# WCE_Power_Backscatter.net
KiCad netlist of a schematic drawn in Altium Designer
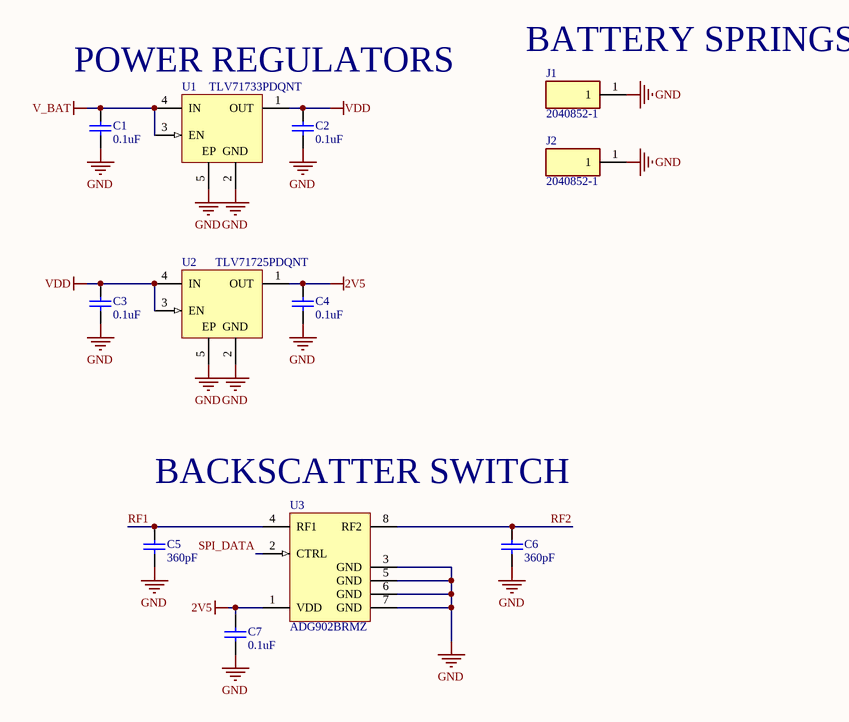
[diagram p0: WCE_Power_Backscatter.SchDoc]

(export (version "E")
  (design (tool "Eeschema 10.0.6"))
  (components
    (comp (ref "C1")
      (value "0.1uF")
      (footprint "CAPC0603X33X15LL03T05")
      (description "Capacitor 0.1 uF 0201 XR5")
      (fields
        (field (name "PART NUMBER") "02016D104KAT2A")
        (field (name "MANUFACTURER") "AVX Interconnect / Elco")
      )
      (libsource (lib "Altium Content Vault") (part "CAP"))
    )
    (comp (ref "C2")
      (value "0.1uF")
      (footprint "CAPC0603X33X15LL03T05")
      (description "Capacitor 0.1 uF 0201 XR5")
      (fields
        (field (name "PART NUMBER") "02016D104KAT2A")
        (field (name "MANUFACTURER") "AVX Interconnect / Elco")
      )
      (libsource (lib "Altium Content Vault") (part "CAP"))
    )
    (comp (ref "C3")
      (value "0.1uF")
      (footprint "CAPC0603X33X15LL03T05")
      (description "Capacitor 0.1 uF 0201 XR5")
      (fields
        (field (name "PART NUMBER") "02016D104KAT2A")
        (field (name "MANUFACTURER") "AVX Interconnect / Elco")
      )
      (libsource (lib "Altium Content Vault") (part "CAP"))
    )
    (comp (ref "C4")
      (value "0.1uF")
      (footprint "CAPC0603X33X15LL03T05")
      (description "Capacitor 0.1 uF 0201 XR5")
      (fields
        (field (name "PART NUMBER") "02016D104KAT2A")
        (field (name "MANUFACTURER") "AVX Interconnect / Elco")
      )
      (libsource (lib "Altium Content Vault") (part "CAP"))
    )
    (comp (ref "C5")
      (value "360pF")
      (footprint "CAPC0603X33X15LL03T05")
      (description "Capacitor 360 pF 0201 XR5")
      (fields
        (field (name "PART NUMBER") "02016D104KAT2A")
        (field (name "MANUFACTURER") "AVX Interconnect / Elco")
      )
      (libsource (lib "Altium Content Vault") (part "CAP"))
    )
    (comp (ref "C6")
      (value "360pF")
      (footprint "CAPC0603X33X15LL03T05")
      (description "Capacitor 360 pF 0201 XR5")
      (fields
        (field (name "PART NUMBER") "02016D104KAT2A")
        (field (name "MANUFACTURER") "AVX Interconnect / Elco")
      )
      (libsource (lib "Altium Content Vault") (part "CAP"))
    )
    (comp (ref "C7")
      (value "0.1uF")
      (footprint "CAPC0603X33X15LL03T05")
      (description "Capacitor 0.1 uF 0201 XR5")
      (fields
        (field (name "PART NUMBER") "02016D104KAT2A")
        (field (name "MANUFACTURER") "AVX Interconnect / Elco")
      )
      (libsource (lib "Altium Content Vault") (part "CAP"))
    )
    (comp (ref "J1")
      (value "2040852-1")
      (footprint "2040852-1")
      (description "TE connectivity 2040852-1 PCB Spring Contact")
      (libsource (lib "WCE_thesis") (part "2040852-1"))
    )
    (comp (ref "J2")
      (value "2040852-1")
      (footprint "2040852-1")
      (description "TE connectivity 2040852-1 PCB Spring Contact")
      (libsource (lib "WCE_thesis") (part "2040852-1"))
    )
    (comp (ref "U1")
      (value "TLV71733PDQNT")
      (footprint "DQN0004A_V")
      (fields (field (name "MANUFACTURER") "Texas Instruments"))
      (libsource (lib "Altium Content Vault") (part "TI-TLV717XXPDQN4"))
    )
    (comp (ref "U2")
      (value "TLV71725PDQNT")
      (footprint "DQN0004A_V")
      (fields (field (name "MANUFACTURER") "Texas Instruments"))
      (libsource (lib "Altium Content Vault") (part "TI-TLV717XXPDQN4"))
    )
    (comp (ref "U3")
      (value "ADG902BRMZ")
      (footprint "ADI-RM-8_L")
      (libsource (lib "Altium Content Vault") (part "ADI-ADG902-RM-8"))
    )
  )
  (nets
    (net (code "2") (name "/RF1") (class "Default")
      (node (ref "C5") (pin "2") (pinfunction "2_2") (pintype "passive"))
      (node (ref "U3") (pin "4") (pinfunction "RF1_4") (pintype "passive"))
    )
    (net (code "3") (name "/RF2") (class "Default")
      (node (ref "C6") (pin "2") (pinfunction "2_2") (pintype "passive"))
      (node (ref "U3") (pin "8") (pinfunction "RF2_8") (pintype "passive"))
    )
    (net (code "4") (name "/SPI_DATA") (class "Default")
      (node (ref "U3") (pin "2") (pinfunction "CTRL_2") (pintype "input"))
    )
    (net (code "5") (name "2V5") (class "Default")
      (node (ref "C4") (pin "2") (pinfunction "2_2") (pintype "passive"))
      (node (ref "C7") (pin "2") (pinfunction "2_2") (pintype "passive"))
      (node (ref "U2") (pin "1") (pinfunction "OUT_1") (pintype "power_in"))
      (node (ref "U3") (pin "1") (pinfunction "VDD_1") (pintype "power_in"))
    )
    (net (code "6") (name "GND") (class "Default")
      (node (ref "C1") (pin "1") (pinfunction "1_1") (pintype "passive"))
      (node (ref "C2") (pin "1") (pinfunction "1_1") (pintype "passive"))
      (node (ref "C3") (pin "1") (pinfunction "1_1") (pintype "passive"))
      (node (ref "C4") (pin "1") (pinfunction "1_1") (pintype "passive"))
      (node (ref "C5") (pin "1") (pinfunction "1_1") (pintype "passive"))
      (node (ref "C6") (pin "1") (pinfunction "1_1") (pintype "passive"))
      (node (ref "C7") (pin "1") (pinfunction "1_1") (pintype "passive"))
      (node (ref "J1") (pin "1") (pinfunction "1_1") (pintype "passive"))
      (node (ref "J2") (pin "1") (pinfunction "1_1") (pintype "passive"))
      (node (ref "U1") (pin "2") (pinfunction "GND_2") (pintype "power_in"))
      (node (ref "U1") (pin "5") (pinfunction "EP_5") (pintype "power_in"))
      (node (ref "U2") (pin "2") (pinfunction "GND_2") (pintype "power_in"))
      (node (ref "U2") (pin "5") (pinfunction "EP_5") (pintype "power_in"))
      (node (ref "U3") (pin "3") (pinfunction "GND_3") (pintype "power_in"))
      (node (ref "U3") (pin "5") (pinfunction "GND_5") (pintype "power_in"))
      (node (ref "U3") (pin "6") (pinfunction "GND_6") (pintype "power_in"))
      (node (ref "U3") (pin "7") (pinfunction "GND_7") (pintype "power_in"))
    )
    (net (code "7") (name "VDD") (class "Default")
      (node (ref "C2") (pin "2") (pinfunction "2_2") (pintype "passive"))
      (node (ref "C3") (pin "2") (pinfunction "2_2") (pintype "passive"))
      (node (ref "U1") (pin "1") (pinfunction "OUT_1") (pintype "power_in"))
      (node (ref "U2") (pin "3") (pinfunction "EN_3") (pintype "input"))
      (node (ref "U2") (pin "4") (pinfunction "IN_4") (pintype "power_in"))
    )
    (net (code "8") (name "V_BAT") (class "Default")
      (node (ref "C1") (pin "2") (pinfunction "2_2") (pintype "passive"))
      (node (ref "U1") (pin "3") (pinfunction "EN_3") (pintype "input"))
      (node (ref "U1") (pin "4") (pinfunction "IN_4") (pintype "power_in"))
    )
  )
)
